# IO_Pheripheral.net
KiCad netlist of a schematic drawn in Altium Designer
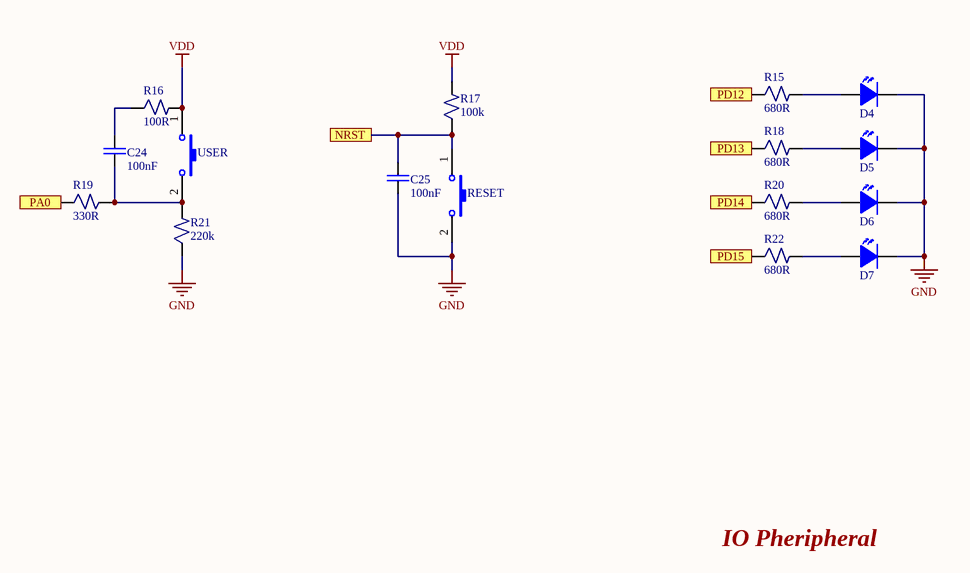
[diagram p0: IO_Pheripheral.SchDoc]

(export (version "E")
  (design (tool "Eeschema 10.0.6"))
  (components
    (comp (ref "C24")
      (value "100nF")
      (footprint "C0805")
      (description "Non-Polarized Capacitor")
      (fields (field (name "Comment") "Cap Non-Pol"))
      (libsource (lib "STM32F4_Board") (part "Cap Non-Pol"))
    )
    (comp (ref "C25")
      (value "100nF")
      (footprint "C0805")
      (description "Non-Polarized Capacitor")
      (fields (field (name "Comment") "Cap Non-Pol"))
      (libsource (lib "STM32F4_Board") (part "Cap Non-Pol"))
    )
    (comp (ref "D4") (value "LED") (footprint "LED0805") (libsource (lib "STM32F4_Board") (part "LED")))
    (comp (ref "D5") (value "LED") (footprint "LED0805") (libsource (lib "STM32F4_Board") (part "LED")))
    (comp (ref "D6") (value "LED") (footprint "LED0805") (libsource (lib "STM32F4_Board") (part "LED")))
    (comp (ref "D7") (value "LED") (footprint "LED0805") (libsource (lib "STM32F4_Board") (part "LED")))
    (comp (ref "R15")
      (value "680R")
      (footprint "R0805")
      (description "Resistor")
      (libsource (lib "STM32F4_Board") (part "Resistor_9"))
    )
    (comp (ref "R16")
      (value "100R")
      (footprint "R0805")
      (description "Resistor")
      (libsource (lib "STM32F4_Board") (part "Resistor_7"))
    )
    (comp (ref "R17")
      (value "100k")
      (footprint "R0805")
      (description "Resistor")
      (libsource (lib "STM32F4_Board") (part "Resistor_6"))
    )
    (comp (ref "R18")
      (value "680R")
      (footprint "R0805")
      (description "Resistor")
      (libsource (lib "STM32F4_Board") (part "Resistor_9"))
    )
    (comp (ref "R19")
      (value "330R")
      (footprint "R0805")
      (description "Resistor")
      (libsource (lib "STM32F4_Board") (part "Resistor_5"))
    )
    (comp (ref "R20")
      (value "680R")
      (footprint "R0805")
      (description "Resistor")
      (libsource (lib "STM32F4_Board") (part "Resistor_9"))
    )
    (comp (ref "R21")
      (value "220k")
      (footprint "R0805")
      (description "Resistor")
      (libsource (lib "STM32F4_Board") (part "Resistor_8"))
    )
    (comp (ref "R22")
      (value "680R")
      (footprint "R0805")
      (description "Resistor")
      (libsource (lib "STM32F4_Board") (part "Resistor_9"))
    )
    (comp (ref "RESET")
      (value "SW-2P-S")
      (footprint "SW2-SMD")
      (description "Switch Small 2 Pin")
      (fields (field (name "PUBLISHER") "Altium Limited"))
      (libsource (lib "STM32F4_Board") (part "SW-2P"))
    )
    (comp (ref "USER")
      (value "SW-2P-S")
      (footprint "SW2-SMD")
      (description "Switch Small 2 Pin")
      (fields (field (name "PUBLISHER") "Altium Limited"))
      (libsource (lib "STM32F4_Board") (part "SW-2P"))
    )
  )
  (nets
    (net (code "1") (name "/NRST") (class "Default")
      (node (ref "C25") (pin "2") (pinfunction "2_2") (pintype "passive"))
      (node (ref "R17") (pin "1") (pintype "passive"))
      (node (ref "RESET") (pin "1") (pinfunction "1_1") (pintype "passive"))
    )
    (net (code "2") (name "/PA0") (class "Default") (node (ref "R19") (pin "1") (pintype "passive")))
    (net (code "3") (name "/PD12") (class "Default") (node (ref "R15") (pin "1") (pintype "passive")))
    (net (code "4") (name "/PD13") (class "Default") (node (ref "R18") (pin "1") (pintype "passive")))
    (net (code "5") (name "/PD14") (class "Default") (node (ref "R20") (pin "1") (pintype "passive")))
    (net (code "6") (name "/PD15") (class "Default") (node (ref "R22") (pin "1") (pintype "passive")))
    (net (code "7") (name "GND") (class "Default")
      (node (ref "C25") (pin "1") (pinfunction "1_1") (pintype "passive"))
      (node (ref "D4") (pin "2") (pinfunction "2_2") (pintype "passive"))
      (node (ref "D5") (pin "2") (pinfunction "2_2") (pintype "passive"))
      (node (ref "D6") (pin "2") (pinfunction "2_2") (pintype "passive"))
      (node (ref "D7") (pin "2") (pinfunction "2_2") (pintype "passive"))
      (node (ref "R21") (pin "1") (pintype "passive"))
      (node (ref "RESET") (pin "2") (pinfunction "2_2") (pintype "passive"))
    )
    (net (code "8") (name "Net-(C24-Pad1)") (class "Default")
      (node (ref "C24") (pin "1") (pinfunction "1_1") (pintype "passive"))
      (node (ref "R19") (pin "2") (pintype "passive"))
      (node (ref "R21") (pin "2") (pintype "passive"))
      (node (ref "USER") (pin "2") (pinfunction "2_2") (pintype "passive"))
    )
    (net (code "9") (name "Net-(C24-Pad2)") (class "Default")
      (node (ref "C24") (pin "2") (pinfunction "2_2") (pintype "passive"))
      (node (ref "R16") (pin "1") (pintype "passive"))
    )
    (net (code "10") (name "Net-(D4-Pad1)") (class "Default")
      (node (ref "D4") (pin "1") (pinfunction "1_1") (pintype "passive"))
      (node (ref "R15") (pin "2") (pintype "passive"))
    )
    (net (code "11") (name "Net-(D5-Pad1)") (class "Default")
      (node (ref "D5") (pin "1") (pinfunction "1_1") (pintype "passive"))
      (node (ref "R18") (pin "2") (pintype "passive"))
    )
    (net (code "12") (name "Net-(D6-Pad1)") (class "Default")
      (node (ref "D6") (pin "1") (pinfunction "1_1") (pintype "passive"))
      (node (ref "R20") (pin "2") (pintype "passive"))
    )
    (net (code "13") (name "Net-(D7-Pad1)") (class "Default")
      (node (ref "D7") (pin "1") (pinfunction "1_1") (pintype "passive"))
      (node (ref "R22") (pin "2") (pintype "passive"))
    )
    (net (code "14") (name "VDD") (class "Default")
      (node (ref "R16") (pin "2") (pintype "passive"))
      (node (ref "R17") (pin "2") (pintype "passive"))
      (node (ref "USER") (pin "1") (pinfunction "1_1") (pintype "passive"))
    )
  )
)
